# Sheet1.net
KiCad netlist of a schematic drawn in Altium Designer
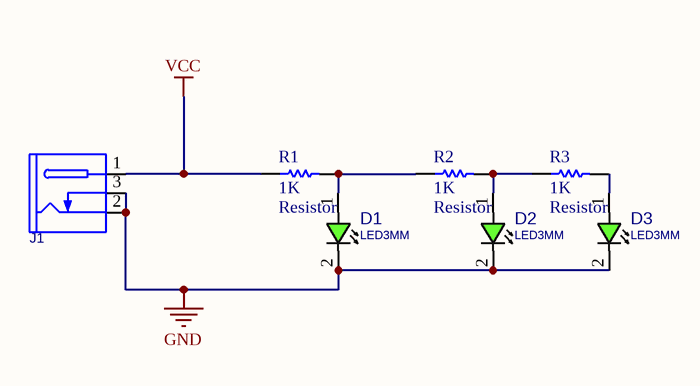
[diagram p0: Sheet1.SchDoc]

(export (version "E")
  (design (tool "Eeschema 10.0.6"))
  (components
    (comp (ref "D1")
      (value "LED3MM")
      (footprint "LED3MM")
      (description "LED, THD, 3MM, GREEN")
      (fields (field (name "MANF") "MANF") (field (name "MANF_P#") "MANF_PART#"))
      (libsource (lib "led(diode)") (part "LED_THD_3MM"))
    )
    (comp (ref "D2")
      (value "LED3MM")
      (footprint "LED3MM")
      (description "LED, THD, 3MM, GREEN")
      (fields (field (name "MANF") "MANF") (field (name "MANF_P#") "MANF_PART#"))
      (libsource (lib "led(diode)") (part "LED_THD_3MM"))
    )
    (comp (ref "D3")
      (value "LED3MM")
      (footprint "LED3MM")
      (description "LED, THD, 3MM, GREEN")
      (fields (field (name "MANF") "MANF") (field (name "MANF_P#") "MANF_PART#"))
      (libsource (lib "led(diode)") (part "LED_THD_3MM"))
    )
    (comp (ref "J1")
      (value "DC_POWER_JACK")
      (footprint "JAC_PWR1")
      (description "CONN, PWR JACK DC, PLUG DIAM 1.0MM RA THD")
      (fields (field (name "MANF") "CUI STACK") (field (name "MANF_P#") "PJ-031CH, PJ-031C"))
      (libsource (lib "conn_powerJack") (part "CONN_PWR_JACKR1"))
    )
    (comp (ref "R1")
      (value "Resistor")
      (footprint "Resistor_0.25w-0.3")
      (fields
        (field (name "ALTIUM_VALUE") "1K")
        (field (name "PUBLISHER") "Seyed Razi Vesali")
        (field (name "EMAIL") "razi.vesali@gmail.com")
      )
      (libsource (lib "Resistors") (part "Resistor"))
    )
    (comp (ref "R2")
      (value "Resistor")
      (footprint "Resistor_0.25w-0.3")
      (fields
        (field (name "ALTIUM_VALUE") "1K")
        (field (name "PUBLISHER") "Seyed Razi Vesali")
        (field (name "EMAIL") "razi.vesali@gmail.com")
      )
      (libsource (lib "Resistors") (part "Resistor"))
    )
    (comp (ref "R3")
      (value "Resistor")
      (footprint "Resistor_0.25w-0.3")
      (fields
        (field (name "ALTIUM_VALUE") "1K")
        (field (name "PUBLISHER") "Seyed Razi Vesali")
        (field (name "EMAIL") "razi.vesali@gmail.com")
      )
      (libsource (lib "Resistors") (part "Resistor"))
    )
  )
  (nets
    (net (code "1") (name "GND") (class "Default")
      (node (ref "D1") (pin "2") (pinfunction "CATHODE_2") (pintype "passive"))
      (node (ref "D2") (pin "2") (pinfunction "CATHODE_2") (pintype "passive"))
      (node (ref "D3") (pin "2") (pinfunction "CATHODE_2") (pintype "passive"))
      (node (ref "J1") (pin "2") (pinfunction "SLEEVE_2") (pintype "power_in"))
      (node (ref "J1") (pin "3") (pinfunction "INSERTION_DET_3") (pintype "power_in"))
    )
    (net (code "2") (name "Net-(D1-ANODE)") (class "Default")
      (node (ref "D1") (pin "1") (pinfunction "ANODE_1") (pintype "passive"))
      (node (ref "R1") (pin "2") (pinfunction "2_2") (pintype "passive"))
      (node (ref "R2") (pin "1") (pinfunction "1_1") (pintype "passive"))
    )
    (net (code "3") (name "Net-(D2-ANODE)") (class "Default")
      (node (ref "D2") (pin "1") (pinfunction "ANODE_1") (pintype "passive"))
      (node (ref "R2") (pin "2") (pinfunction "2_2") (pintype "passive"))
      (node (ref "R3") (pin "1") (pinfunction "1_1") (pintype "passive"))
    )
    (net (code "4") (name "Net-(D3-ANODE)") (class "Default")
      (node (ref "D3") (pin "1") (pinfunction "ANODE_1") (pintype "passive"))
      (node (ref "R3") (pin "2") (pinfunction "2_2") (pintype "passive"))
    )
    (net (code "5") (name "VCC") (class "Default")
      (node (ref "J1") (pin "1") (pinfunction "TIP_1") (pintype "power_in"))
      (node (ref "R1") (pin "1") (pinfunction "1_1") (pintype "passive"))
    )
  )
)
